# motor_Controller3.net
KiCad netlist of a schematic drawn in EAGLE
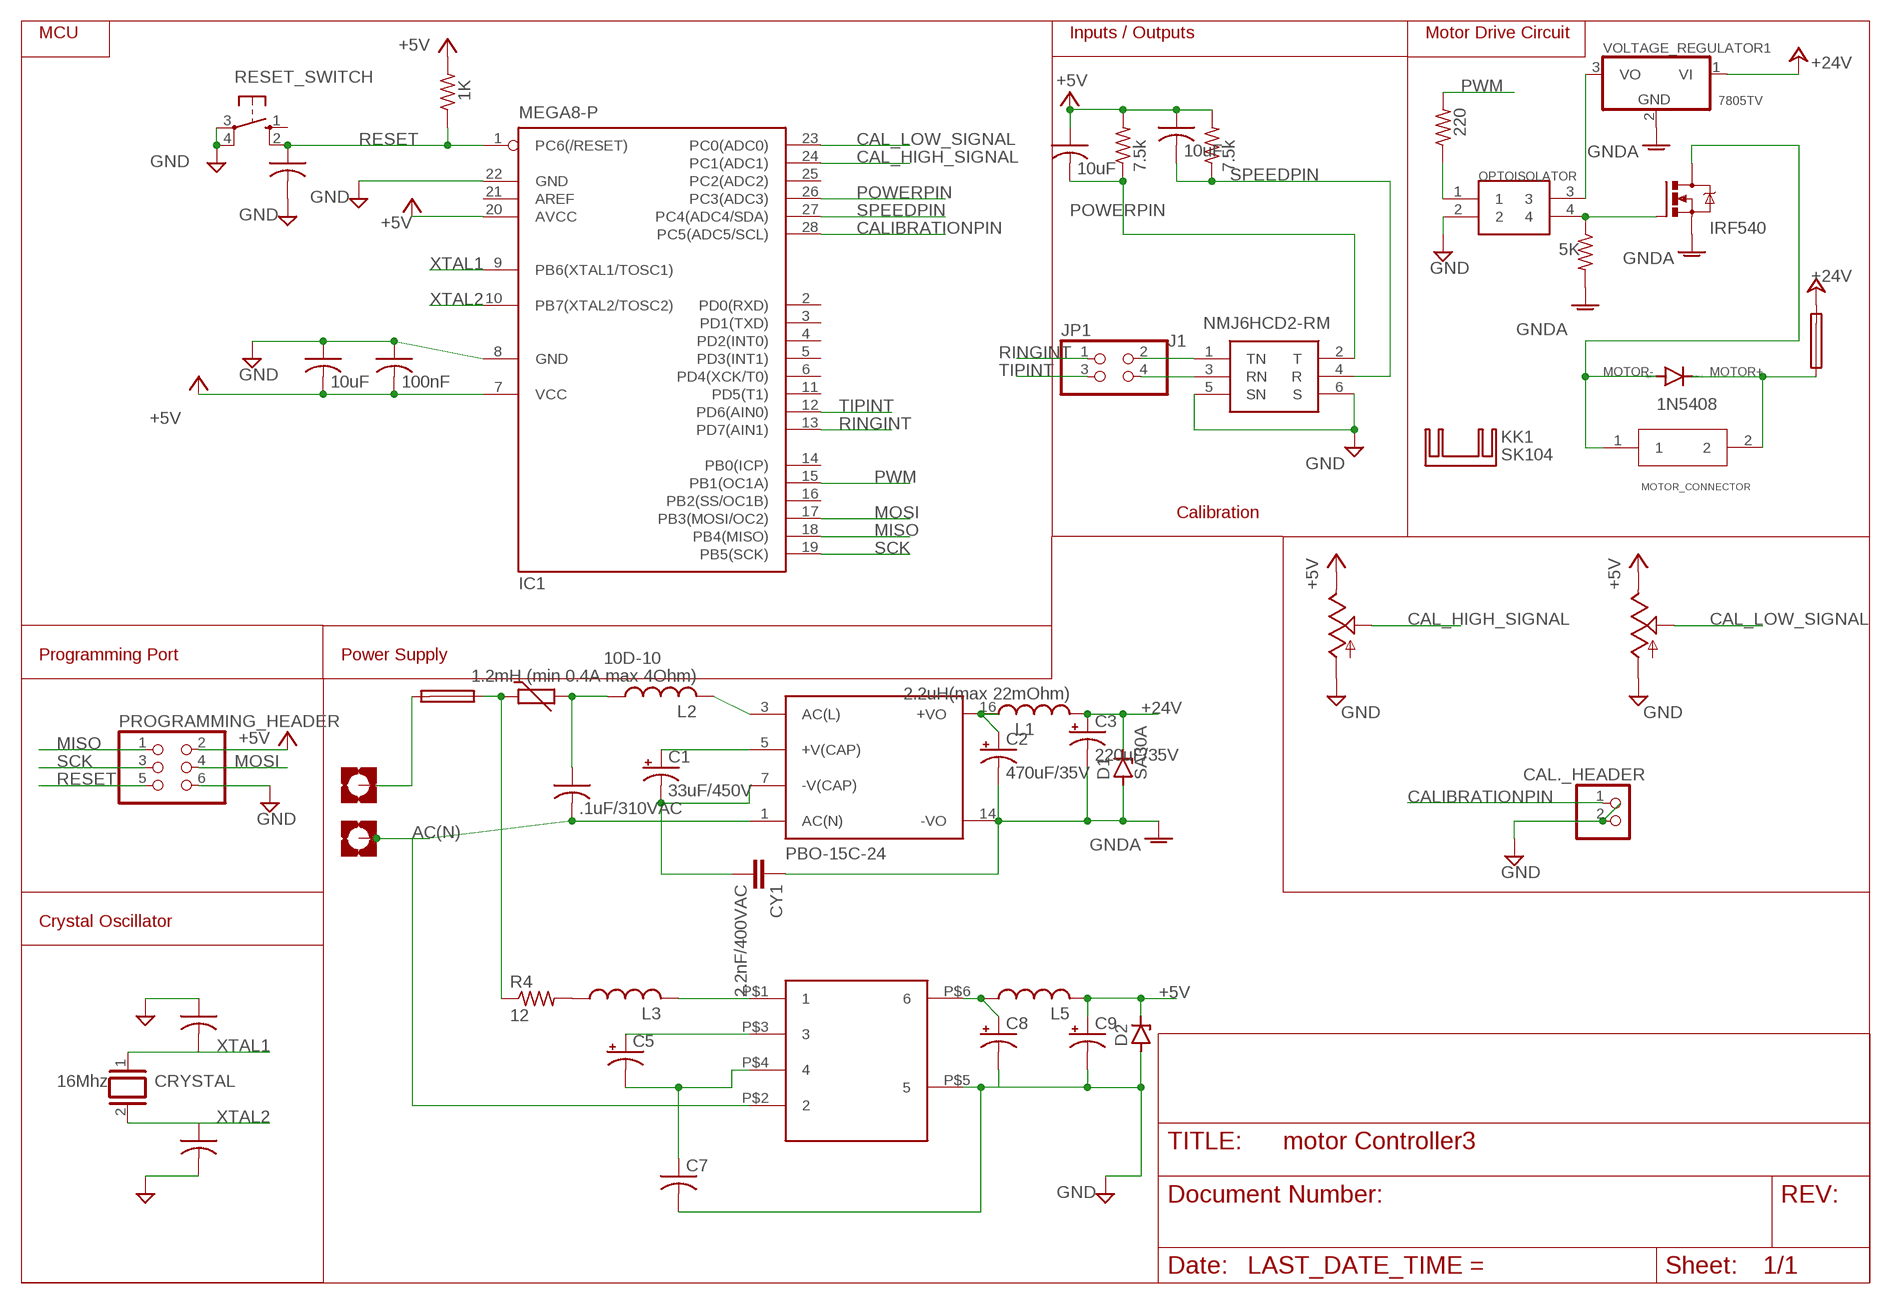
[diagram p0: schematic, sheet 1]

(export (version "E")
  (design (tool "Eeschema 10.0.6"))
  (components
    (comp (ref "1N5408")
      (value "1N5408")
      (footprint "eagle-import:DO201-15")
      (libsource (lib "eagle-import") (part "1N5400"))
    )
    (comp (ref "C1")
      (value "33uF/450V")
      (footprint "eagle-import:E5-13")
      (libsource (lib "eagle-import") (part "CPOL-USE5-13"))
    )
    (comp (ref "C2")
      (value "470uF/35V")
      (footprint "eagle-import:E5-10,5")
      (libsource (lib "eagle-import") (part "CPOL-USE5-10.5"))
    )
    (comp (ref "C3")
      (value "220uF/35V")
      (footprint "eagle-import:E5-10,5")
      (libsource (lib "eagle-import") (part "CPOL-USE5-10.5"))
    )
    (comp (ref "C4")
      (value ".1uF/310VAC")
      (footprint "eagle-import:C150-091X182")
      (libsource (lib "eagle-import") (part "C-US150-091X182"))
    )
    (comp (ref "C5")
      (value "CPOL-USE5-10.5")
      (footprint "eagle-import:E5-10,5")
      (libsource (lib "eagle-import") (part "CPOL-USE5-10.5"))
    )
    (comp (ref "C6")
      (value "C-US025-024X044")
      (footprint "eagle-import:C025-024X044")
      (libsource (lib "eagle-import") (part "C-US025-024X044"))
    )
    (comp (ref "C7")
      (value "C-US075-052X106")
      (footprint "eagle-import:C075-052X106")
      (libsource (lib "eagle-import") (part "C-US075-052X106"))
    )
    (comp (ref "C8")
      (value "CPOL-USE2.5-6")
      (footprint "eagle-import:E2,5-6")
      (libsource (lib "eagle-import") (part "CPOL-USE2.5-6"))
    )
    (comp (ref "C9")
      (value "CPOL-USE3.5-8")
      (footprint "eagle-import:E3,5-8")
      (libsource (lib "eagle-import") (part "CPOL-USE3.5-8"))
    )
    (comp (ref "C10")
      (value "10uF")
      (footprint "eagle-import:C025-024X044")
      (libsource (lib "eagle-import") (part "C-US025-024X044"))
    )
    (comp (ref "C11")
      (value "C-US025-024X044")
      (footprint "eagle-import:C025-024X044")
      (libsource (lib "eagle-import") (part "C-US025-024X044"))
    )
    (comp (ref "C12")
      (value "10uF")
      (footprint "eagle-import:C025-024X044")
      (libsource (lib "eagle-import") (part "C-US025-024X044"))
    )
    (comp (ref "C13")
      (value "10uF")
      (footprint "eagle-import:C025-024X044")
      (libsource (lib "eagle-import") (part "C-US025-024X044"))
    )
    (comp (ref "C14")
      (value "100nF")
      (footprint "eagle-import:C025-024X044")
      (libsource (lib "eagle-import") (part "C-US025-024X044"))
    )
    (comp (ref "C15")
      (value "C-US025-024X044")
      (footprint "eagle-import:C025-024X044")
      (libsource (lib "eagle-import") (part "C-US025-024X044"))
    )
    (comp (ref "CAL._HEADER")
      (value "PINHD-1X2")
      (footprint "eagle-import:1X02")
      (libsource (lib "eagle-import") (part "PINHD-1X2"))
    )
    (comp (ref "CRYSTAL")
      (value "16Mhz")
      (footprint "eagle-import:QS")
      (libsource (lib "eagle-import") (part "XTAL/S"))
    )
    (comp (ref "CY1")
      (value "2.2nF/400VAC")
      (footprint "eagle-import:YC10B4")
      (libsource (lib "eagle-import") (part "CYYC10B4"))
    )
    (comp (ref "D1")
      (value "SA30A")
      (footprint "eagle-import:ZDIO-7.5")
      (libsource (lib "eagle-import") (part "ZENER-DIODEZD-7.5"))
    )
    (comp (ref "D2")
      (value "ZENER-DIODEZD-7.5")
      (footprint "eagle-import:ZDIO-7.5")
      (libsource (lib "eagle-import") (part "ZENER-DIODEZD-7.5"))
    )
    (comp (ref "F1")
      (value "FUSESH22,5")
      (footprint "eagle-import:SH22,5")
      (libsource (lib "eagle-import") (part "FUSESH22,5"))
    )
    (comp (ref "F2")
      (value "1A/300V")
      (footprint "eagle-import:SH22,5")
      (libsource (lib "eagle-import") (part "FUSESH22,5"))
    )
    (comp (ref "FAST")
      (value "TRIM_US-CT6")
      (footprint "eagle-import:CT6")
      (libsource (lib "eagle-import") (part "TRIM_US-CT6"))
    )
    (comp (ref "H1")
      (value "MOUNT-PAD-SQUARE3.6")
      (footprint "eagle-import:3,6-PAD-SQUARE")
      (libsource (lib "eagle-import") (part "MOUNT-PAD-SQUARE3.6"))
    )
    (comp (ref "H2")
      (value "MOUNT-PAD-SQUARE3.6")
      (footprint "eagle-import:3,6-PAD-SQUARE")
      (libsource (lib "eagle-import") (part "MOUNT-PAD-SQUARE3.6"))
    )
    (comp (ref "IC1")
      (value "MEGA8-P")
      (footprint "eagle-import:DIL28-3")
      (libsource (lib "eagle-import") (part "MEGA8-P"))
    )
    (comp (ref "J1")
      (value "NMJ6HCD2-RM")
      (footprint "eagle-import:NMJ6HCD2RM")
      (fields (field (name "MOUSER_PART_NUMBER") "568-NMJ6HCD2-RM"))
      (libsource (lib "eagle-import") (part "NMJ6HCD2-RM"))
    )
    (comp (ref "JP1")
      (value "PINHD-2X2")
      (footprint "eagle-import:2X02")
      (libsource (lib "eagle-import") (part "PINHD-2X2"))
    )
    (comp (ref "KK1")
      (value "SK104")
      (footprint "eagle-import:SK104")
      (libsource (lib "eagle-import") (part "SK104"))
    )
    (comp (ref "L1")
      (value "2.2uH(max 22mOhm)")
      (footprint "eagle-import:TJ5-U1")
      (libsource (lib "eagle-import") (part "L-USTJ5-U1"))
    )
    (comp (ref "L2")
      (value "1.2mH (min 0.4A max 4Ohm)")
      (footprint "eagle-import:6000-XXXX-RC")
      (libsource (lib "eagle-import") (part "L-US6000-XXX-RC"))
    )
    (comp (ref "L3")
      (value "L-US6000-XXX-RC")
      (footprint "eagle-import:6000-XXXX-RC")
      (libsource (lib "eagle-import") (part "L-US6000-XXX-RC"))
    )
    (comp (ref "L5")
      (value "L-US0207/2V")
      (footprint "eagle-import:0207_2V")
      (libsource (lib "eagle-import") (part "L-US0207/2V"))
    )
    (comp (ref "MOTOR_CONNECTOR")
      (value "641963-1")
      (footprint "eagle-import:641963-1_TYC")
      (libsource (lib "eagle-import") (part "641963-1"))
    )
    (comp (ref "OPTOISOLATOR")
      (value "SFH619A")
      (footprint "eagle-import:SFH619A")
      (fields (field (name "OPTOISOLATOR") "SFH619A"))
      (libsource (lib "eagle-import") (part "SFH619A-ND"))
    )
    (comp (ref "PROGRAMMING_HEADER")
      (value "PINHD-2X3")
      (footprint "eagle-import:2X03")
      (libsource (lib "eagle-import") (part "PINHD-2X3"))
    )
    (comp (ref "PS1")
      (value "PBO-15C-24")
      (footprint "eagle-import:CONV_PBO-15C-24")
      (fields (field (name "MF") "CUI Inc."))
      (libsource (lib "eagle-import") (part "PBO-15C-24"))
    )
    (comp (ref "Q1")
      (value "IRF540")
      (footprint "eagle-import:TO220BV")
      (libsource (lib "eagle-import") (part "IRF540"))
    )
    (comp (ref "R1")
      (value "10D-10")
      (footprint "eagle-import:R-7,5")
      (libsource (lib "eagle-import") (part "THERMISTOR-7,5"))
    )
    (comp (ref "R2")
      (value "1K")
      (footprint "eagle-import:0204_7")
      (libsource (lib "eagle-import") (part "R-US_0204/7"))
    )
    (comp (ref "R3")
      (value "7.5k")
      (footprint "eagle-import:0204_7")
      (libsource (lib "eagle-import") (part "R-US_0204/7"))
    )
    (comp (ref "R4")
      (value "12")
      (footprint "eagle-import:0617_22")
      (libsource (lib "eagle-import") (part "R-US_0617/22"))
    )
    (comp (ref "R5")
      (value "220")
      (footprint "eagle-import:0204_7")
      (libsource (lib "eagle-import") (part "R-US_0204/7"))
    )
    (comp (ref "R6")
      (value "5K")
      (footprint "eagle-import:0204_7")
      (libsource (lib "eagle-import") (part "R-US_0204/7"))
    )
    (comp (ref "R7")
      (value "7.5k")
      (footprint "eagle-import:0204_7")
      (libsource (lib "eagle-import") (part "R-US_0204/7"))
    )
    (comp (ref "RESET_SWITCH")
      (value "10-XX")
      (footprint "eagle-import:B3F-10XX")
      (fields (field (name "MPN") "B3F-1000"))
      (libsource (lib "eagle-import") (part "10-XX"))
    )
    (comp (ref "SLOW")
      (value "TRIM_US-CT6")
      (footprint "eagle-import:CT6")
      (libsource (lib "eagle-import") (part "TRIM_US-CT6"))
    )
    (comp (ref "U$1")
      (value "L503-13B05R$3")
      (footprint "eagle-import:LS03-13BO5R3")
      (libsource (lib "eagle-import") (part "L503-13B05R$3"))
    )
    (comp (ref "VOLTAGE_REGULATOR1")
      (value "7805TV")
      (footprint "eagle-import:TO220V")
      (libsource (lib "eagle-import") (part "78TV05"))
    )
  )
  (nets
    (net (code "1") (name "+5V") (class "Default")
      (node (ref "C10") (pin "1") (pinfunction "1_1") (pintype "passive"))
      (node (ref "C12") (pin "1") (pinfunction "1_1") (pintype "passive"))
      (node (ref "C13") (pin "2") (pinfunction "2_2") (pintype "passive"))
      (node (ref "C14") (pin "2") (pinfunction "2_2") (pintype "passive"))
      (node (ref "C9") (pin "+") (pinfunction "+_+") (pintype "passive"))
      (node (ref "D2") (pin "C") (pinfunction "C_C") (pintype "passive"))
      (node (ref "FAST") (pin "E") (pinfunction "E_E") (pintype "passive"))
      (node (ref "IC1") (pin "20") (pinfunction "AVCC_20") (pintype "power_in"))
      (node (ref "IC1") (pin "7") (pinfunction "VCC_7") (pintype "power_in"))
      (node (ref "L5") (pin "2") (pinfunction "2_2") (pintype "passive"))
      (node (ref "PROGRAMMING_HEADER") (pin "2") (pinfunction "2_2") (pintype "passive"))
      (node (ref "R2") (pin "2") (pinfunction "2_2") (pintype "passive"))
      (node (ref "R3") (pin "2") (pinfunction "2_2") (pintype "passive"))
      (node (ref "R7") (pin "2") (pinfunction "2_2") (pintype "passive"))
      (node (ref "SLOW") (pin "E") (pinfunction "E_E") (pintype "passive"))
    )
    (net (code "2") (name "+24V") (class "Default")
      (node (ref "C3") (pin "+") (pinfunction "+_+") (pintype "passive"))
      (node (ref "D1") (pin "C") (pinfunction "C_C") (pintype "passive"))
      (node (ref "F1") (pin "2") (pinfunction "2_2") (pintype "passive"))
      (node (ref "L1") (pin "2") (pinfunction "2_2") (pintype "passive"))
      (node (ref "VOLTAGE_REGULATOR1") (pin "1") (pinfunction "VI_1") (pintype "input"))
    )
    (net (code "3") (name "/AC(N)") (class "Default")
      (node (ref "C4") (pin "2") (pinfunction "2_2") (pintype "passive"))
      (node (ref "H2") (pin "B3,6") (pinfunction "MOUNT_B3,6") (pintype "passive"))
      (node (ref "PS1") (pin "1") (pinfunction "AC(N)_1") (pintype "input"))
      (node (ref "U$1") (pin "P$2") (pinfunction "2_P$2") (pintype "bidirectional"))
    )
    (net (code "4") (name "/CALIBRATIONPIN") (class "Default")
      (node (ref "CAL._HEADER") (pin "1") (pinfunction "1_1") (pintype "passive"))
      (node (ref "IC1") (pin "28") (pinfunction "PC5(ADC5/SCL)_28") (pintype "bidirectional"))
    )
    (net (code "5") (name "/CAL_HIGH_SIGNAL") (class "Default")
      (node (ref "FAST") (pin "S") (pinfunction "S_S") (pintype "passive"))
      (node (ref "IC1") (pin "24") (pinfunction "PC1(ADC1)_24") (pintype "bidirectional"))
    )
    (net (code "6") (name "/CAL_LOW_SIGNAL") (class "Default")
      (node (ref "IC1") (pin "23") (pinfunction "PC0(ADC0)_23") (pintype "bidirectional"))
      (node (ref "SLOW") (pin "S") (pinfunction "S_S") (pintype "passive"))
    )
    (net (code "7") (name "/MISO") (class "Default")
      (node (ref "IC1") (pin "18") (pinfunction "PB4(MISO)_18") (pintype "bidirectional"))
      (node (ref "PROGRAMMING_HEADER") (pin "1") (pinfunction "1_1") (pintype "passive"))
    )
    (net (code "8") (name "/MOSI") (class "Default")
      (node (ref "IC1") (pin "17") (pinfunction "PB3(MOSI/OC2)_17") (pintype "bidirectional"))
      (node (ref "PROGRAMMING_HEADER") (pin "4") (pinfunction "4_4") (pintype "passive"))
    )
    (net (code "9") (name "/MOTOR+") (class "Default")
      (node (ref "1N5408") (pin "C") (pinfunction "C_C") (pintype "passive"))
      (node (ref "F1") (pin "1") (pinfunction "1_1") (pintype "passive"))
      (node (ref "MOTOR_CONNECTOR") (pin "2") (pinfunction "2_2") (pintype "passive"))
    )
    (net (code "10") (name "/MOTOR-") (class "Default")
      (node (ref "1N5408") (pin "A") (pinfunction "A_A") (pintype "passive"))
      (node (ref "MOTOR_CONNECTOR") (pin "1") (pinfunction "1_1") (pintype "passive"))
      (node (ref "Q1") (pin "D") (pinfunction "D_D") (pintype "passive"))
    )
    (net (code "11") (name "/POWERPIN") (class "Default")
      (node (ref "C10") (pin "2") (pinfunction "2_2") (pintype "passive"))
      (node (ref "IC1") (pin "26") (pinfunction "PC3(ADC3)_26") (pintype "bidirectional"))
      (node (ref "J1") (pin "2") (pinfunction "T_2") (pintype "bidirectional"))
      (node (ref "R3") (pin "1") (pinfunction "1_1") (pintype "passive"))
    )
    (net (code "12") (name "/PWM") (class "Default")
      (node (ref "IC1") (pin "15") (pinfunction "PB1(OC1A)_15") (pintype "bidirectional"))
      (node (ref "R5") (pin "2") (pinfunction "2_2") (pintype "passive"))
    )
    (net (code "13") (name "/RESET") (class "Default")
      (node (ref "C11") (pin "1") (pinfunction "1_1") (pintype "passive"))
      (node (ref "IC1") (pin "1") (pinfunction "PC6(/RESET)_1") (pintype "bidirectional"))
      (node (ref "PROGRAMMING_HEADER") (pin "5") (pinfunction "5_5") (pintype "passive"))
      (node (ref "R2") (pin "1") (pinfunction "1_1") (pintype "passive"))
      (node (ref "RESET_SWITCH") (pin "2") (pinfunction "S1_2") (pintype "passive"))
    )
    (net (code "14") (name "/RINGINT") (class "Default")
      (node (ref "IC1") (pin "13") (pinfunction "PD7(AIN1)_13") (pintype "bidirectional"))
      (node (ref "JP1") (pin "1") (pinfunction "1_1") (pintype "passive"))
    )
    (net (code "15") (name "/SCK") (class "Default")
      (node (ref "IC1") (pin "19") (pinfunction "PB5(SCK)_19") (pintype "bidirectional"))
      (node (ref "PROGRAMMING_HEADER") (pin "3") (pinfunction "3_3") (pintype "passive"))
    )
    (net (code "16") (name "/SPEEDPIN") (class "Default")
      (node (ref "C12") (pin "2") (pinfunction "2_2") (pintype "passive"))
      (node (ref "IC1") (pin "27") (pinfunction "PC4(ADC4/SDA)_27") (pintype "bidirectional"))
      (node (ref "J1") (pin "4") (pinfunction "R_4") (pintype "bidirectional"))
      (node (ref "R7") (pin "1") (pinfunction "1_1") (pintype "passive"))
    )
    (net (code "17") (name "/TIPINT") (class "Default")
      (node (ref "IC1") (pin "12") (pinfunction "PD6(AIN0)_12") (pintype "bidirectional"))
      (node (ref "JP1") (pin "3") (pinfunction "3_3") (pintype "passive"))
    )
    (net (code "18") (name "/XTAL1") (class "Default")
      (node (ref "C15") (pin "2") (pinfunction "2_2") (pintype "passive"))
      (node (ref "CRYSTAL") (pin "1") (pinfunction "1_1") (pintype "passive"))
      (node (ref "IC1") (pin "9") (pinfunction "PB6(XTAL1/TOSC1)_9") (pintype "bidirectional"))
    )
    (net (code "19") (name "/XTAL2") (class "Default")
      (node (ref "C6") (pin "1") (pinfunction "1_1") (pintype "passive"))
      (node (ref "CRYSTAL") (pin "2") (pinfunction "2_2") (pintype "passive"))
      (node (ref "IC1") (pin "10") (pinfunction "PB7(XTAL2/TOSC2)_10") (pintype "bidirectional"))
    )
    (net (code "20") (name "GND") (class "Default")
      (node (ref "C11") (pin "2") (pinfunction "2_2") (pintype "passive"))
      (node (ref "C13") (pin "1") (pinfunction "1_1") (pintype "passive"))
      (node (ref "C14") (pin "1") (pinfunction "1_1") (pintype "passive"))
      (node (ref "C15") (pin "1") (pinfunction "1_1") (pintype "passive"))
      (node (ref "C6") (pin "2") (pinfunction "2_2") (pintype "passive"))
      (node (ref "C7") (pin "2") (pinfunction "2_2") (pintype "passive"))
      (node (ref "C8") (pin "-") (pinfunction "-_-") (pintype "passive"))
      (node (ref "C9") (pin "-") (pinfunction "-_-") (pintype "passive"))
      (node (ref "CAL._HEADER") (pin "2") (pinfunction "2_2") (pintype "passive"))
      (node (ref "D2") (pin "A") (pinfunction "A_A") (pintype "passive"))
      (node (ref "FAST") (pin "A") (pinfunction "A_A") (pintype "passive"))
      (node (ref "IC1") (pin "22") (pinfunction "GND_22") (pintype "power_in"))
      (node (ref "IC1") (pin "8") (pinfunction "GND_8") (pintype "power_in"))
      (node (ref "J1") (pin "5") (pinfunction "SN_5") (pintype "bidirectional"))
      (node (ref "J1") (pin "6") (pinfunction "S_6") (pintype "bidirectional"))
      (node (ref "OPTOISOLATOR") (pin "2") (pinfunction "2_2") (pintype "bidirectional"))
      (node (ref "PROGRAMMING_HEADER") (pin "6") (pinfunction "6_6") (pintype "passive"))
      (node (ref "RESET_SWITCH") (pin "3") (pinfunction "P_3") (pintype "passive"))
      (node (ref "RESET_SWITCH") (pin "4") (pinfunction "P1_4") (pintype "passive"))
      (node (ref "SLOW") (pin "A") (pinfunction "A_A") (pintype "passive"))
      (node (ref "U$1") (pin "P$5") (pinfunction "5_P$5") (pintype "bidirectional"))
    )
    (net (code "21") (name "GNDA") (class "Default")
      (node (ref "C2") (pin "-") (pinfunction "-_-") (pintype "passive"))
      (node (ref "C3") (pin "-") (pinfunction "-_-") (pintype "passive"))
      (node (ref "CY1") (pin "1") (pinfunction "1_1") (pintype "passive"))
      (node (ref "D1") (pin "A") (pinfunction "A_A") (pintype "passive"))
      (node (ref "PS1") (pin "14") (pinfunction "-VO_14") (pintype "output"))
      (node (ref "Q1") (pin "S") (pinfunction "S_S") (pintype "passive"))
      (node (ref "R6") (pin "2") (pinfunction "2_2") (pintype "passive"))
      (node (ref "VOLTAGE_REGULATOR1") (pin "2") (pinfunction "GND_2") (pintype "passive"))
    )
    (net (code "22") (name "Net-(C4-Pad1)") (class "Default")
      (node (ref "C4") (pin "1") (pinfunction "1_1") (pintype "passive"))
      (node (ref "L2") (pin "1") (pinfunction "1_1") (pintype "passive"))
      (node (ref "R1") (pin "2") (pinfunction "2_2") (pintype "passive"))
    )
    (net (code "23") (name "Net-(F2-Pad1)") (class "Default")
      (node (ref "F2") (pin "1") (pinfunction "1_1") (pintype "passive"))
      (node (ref "R1") (pin "1") (pinfunction "1_1") (pintype "passive"))
      (node (ref "R4") (pin "1") (pinfunction "1_1") (pintype "passive"))
    )
    (net (code "24") (name "Net-(H1-MOUNT)") (class "Default")
      (node (ref "F2") (pin "2") (pinfunction "2_2") (pintype "passive"))
      (node (ref "H1") (pin "B3,6") (pinfunction "MOUNT_B3,6") (pintype "passive"))
    )
    (net (code "25") (name "Net-(J1-RN)") (class "Default")
      (node (ref "J1") (pin "3") (pinfunction "RN_3") (pintype "bidirectional"))
      (node (ref "JP1") (pin "4") (pinfunction "4_4") (pintype "passive"))
    )
    (net (code "26") (name "Net-(J1-TN)") (class "Default")
      (node (ref "J1") (pin "1") (pinfunction "TN_1") (pintype "bidirectional"))
      (node (ref "JP1") (pin "2") (pinfunction "2_2") (pintype "passive"))
    )
    (net (code "27") (name "Net-(L3-Pad1)") (class "Default")
      (node (ref "L3") (pin "1") (pinfunction "1_1") (pintype "passive"))
      (node (ref "R4") (pin "2") (pinfunction "2_2") (pintype "passive"))
    )
    (net (code "28") (name "Net-(OPTOISOLATOR-Pad1)") (class "Default")
      (node (ref "OPTOISOLATOR") (pin "1") (pinfunction "1_1") (pintype "bidirectional"))
      (node (ref "R5") (pin "1") (pinfunction "1_1") (pintype "passive"))
    )
    (net (code "29") (name "Net-(OPTOISOLATOR-Pad4)") (class "Default")
      (node (ref "OPTOISOLATOR") (pin "4") (pinfunction "4_4") (pintype "bidirectional"))
      (node (ref "Q1") (pin "G") (pinfunction "G_G") (pintype "passive"))
      (node (ref "R6") (pin "1") (pinfunction "1_1") (pintype "passive"))
    )
    (net (code "30") (name "Net-(PS1-+V(CAP))") (class "Default")
      (node (ref "C1") (pin "+") (pinfunction "+_+") (pintype "passive"))
      (node (ref "PS1") (pin "5") (pinfunction "+V(CAP)_5") (pintype "passive"))
    )
    (net (code "31") (name "Net-(PS1-+VO)") (class "Default")
      (node (ref "C2") (pin "+") (pinfunction "+_+") (pintype "passive"))
      (node (ref "L1") (pin "1") (pinfunction "1_1") (pintype "passive"))
      (node (ref "PS1") (pin "16") (pinfunction "+VO_16") (pintype "output"))
    )
    (net (code "32") (name "Net-(PS1--V(CAP))") (class "Default")
      (node (ref "C1") (pin "-") (pinfunction "-_-") (pintype "passive"))
      (node (ref "CY1") (pin "2") (pinfunction "2_2") (pintype "passive"))
      (node (ref "PS1") (pin "7") (pinfunction "-V(CAP)_7") (pintype "passive"))
    )
    (net (code "33") (name "Net-(PS1-AC(L))") (class "Default")
      (node (ref "L2") (pin "2") (pinfunction "2_2") (pintype "passive"))
      (node (ref "PS1") (pin "3") (pinfunction "AC(L)_3") (pintype "input"))
    )
    (net (code "34") (name "Net-(U$1-1)") (class "Default")
      (node (ref "L3") (pin "2") (pinfunction "2_2") (pintype "passive"))
      (node (ref "U$1") (pin "P$1") (pinfunction "1_P$1") (pintype "bidirectional"))
    )
    (net (code "35") (name "Net-(U$1-3)") (class "Default")
      (node (ref "C5") (pin "+") (pinfunction "+_+") (pintype "passive"))
      (node (ref "U$1") (pin "P$3") (pinfunction "3_P$3") (pintype "bidirectional"))
    )
    (net (code "36") (name "Net-(U$1-4)") (class "Default")
      (node (ref "C5") (pin "-") (pinfunction "-_-") (pintype "passive"))
      (node (ref "C7") (pin "1") (pinfunction "1_1") (pintype "passive"))
      (node (ref "U$1") (pin "P$4") (pinfunction "4_P$4") (pintype "bidirectional"))
    )
    (net (code "37") (name "Net-(U$1-6)") (class "Default")
      (node (ref "C8") (pin "+") (pinfunction "+_+") (pintype "passive"))
      (node (ref "L5") (pin "1") (pinfunction "1_1") (pintype "passive"))
      (node (ref "U$1") (pin "P$6") (pinfunction "6_P$6") (pintype "bidirectional"))
    )
    (net (code "38") (name "Net-(VOLTAGE_REGULATOR1-VO)") (class "Default")
      (node (ref "OPTOISOLATOR") (pin "3") (pinfunction "3_3") (pintype "bidirectional"))
      (node (ref "VOLTAGE_REGULATOR1") (pin "3") (pinfunction "VO_3") (pintype "passive"))
    )
    (net (code "39") (name "unconnected-(IC1-AREF-Pad21)") (class "Default")
      (node (ref "IC1") (pin "21") (pinfunction "AREF_21") (pintype "passive"))
    )
    (net (code "40") (name "unconnected-(IC1-PB0(ICP)-Pad14)") (class "Default")
      (node (ref "IC1") (pin "14") (pinfunction "PB0(ICP)_14") (pintype "bidirectional"))
    )
    (net (code "41") (name "unconnected-(IC1-PB2(SS{slash}OC1B)-Pad16)") (class "Default")
      (node (ref "IC1") (pin "16") (pinfunction "PB2(SS/OC1B)_16") (pintype "bidirectional"))
    )
    (net (code "42") (name "unconnected-(IC1-PC2(ADC2)-Pad25)") (class "Default")
      (node (ref "IC1") (pin "25") (pinfunction "PC2(ADC2)_25") (pintype "bidirectional"))
    )
    (net (code "43") (name "unconnected-(IC1-PD0(RXD)-Pad2)") (class "Default")
      (node (ref "IC1") (pin "2") (pinfunction "PD0(RXD)_2") (pintype "bidirectional"))
    )
    (net (code "44") (name "unconnected-(IC1-PD1(TXD)-Pad3)") (class "Default")
      (node (ref "IC1") (pin "3") (pinfunction "PD1(TXD)_3") (pintype "bidirectional"))
    )
    (net (code "45") (name "unconnected-(IC1-PD2(INT0)-Pad4)") (class "Default")
      (node (ref "IC1") (pin "4") (pinfunction "PD2(INT0)_4") (pintype "bidirectional"))
    )
    (net (code "46") (name "unconnected-(IC1-PD3(INT1)-Pad5)") (class "Default")
      (node (ref "IC1") (pin "5") (pinfunction "PD3(INT1)_5") (pintype "bidirectional"))
    )
    (net (code "47") (name "unconnected-(IC1-PD4(XCK{slash}T0)-Pad6)") (class "Default")
      (node (ref "IC1") (pin "6") (pinfunction "PD4(XCK/T0)_6") (pintype "bidirectional"))
    )
    (net (code "48") (name "unconnected-(IC1-PD5(T1)-Pad11)") (class "Default")
      (node (ref "IC1") (pin "11") (pinfunction "PD5(T1)_11") (pintype "bidirectional"))
    )
    (net (code "49") (name "unconnected-(RESET_SWITCH-S-Pad1)") (class "Default")
      (node (ref "RESET_SWITCH") (pin "1") (pinfunction "S_1") (pintype "passive"))
    )
  )
)
